# 12V_POWER_BULKHEAD.net
KiCad netlist of a schematic drawn in Altium Designer
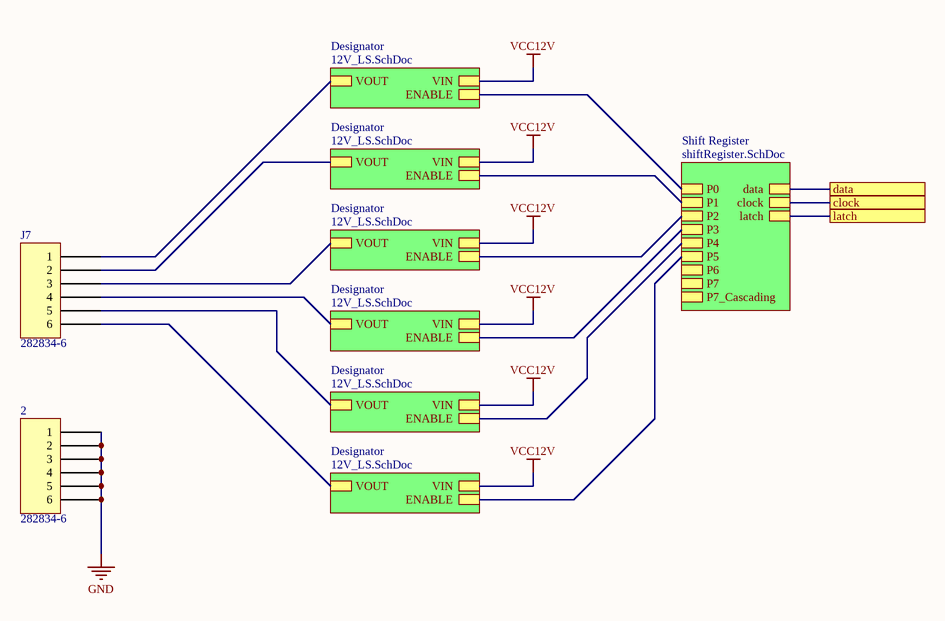
[diagram p0: 12V_POWER_BULKHEAD.SchDoc]

(export (version "E")
  (design (tool "Eeschema 10.0.6"))
  (components
    (comp (ref "2")
      (value "282834-6")
      (footprint "TE 282834-6")
      (description "TERM BLK 6P SIDE ENT 2.54MM PCB")
      (fields (field (name "MANUFACTURER") "TE Connectivity AMP Connectors") (field (name "VOLTAGE") "150V"))
      (libsource (lib "Celestial Altium Library - altium_library") (part "6 Pin"))
    )
    (comp (ref "J7")
      (value "282834-6")
      (footprint "TE 282834-6")
      (description "TERM BLK 6P SIDE ENT 2.54MM PCB")
      (fields (field (name "MANUFACTURER") "TE Connectivity AMP Connectors") (field (name "VOLTAGE") "150V"))
      (libsource (lib "Celestial Altium Library - altium_library") (part "6 Pin"))
    )
  )
  (nets
    (net (code "10") (name "/VOUT") (class "Default")
      (node (ref "J7") (pin "1") (pinfunction "1_1") (pintype "passive"))
    )
    (net (code "11") (name "/VOUT_1") (class "Default")
      (node (ref "J7") (pin "2") (pinfunction "2_2") (pintype "passive"))
    )
    (net (code "12") (name "/VOUT_2") (class "Default")
      (node (ref "J7") (pin "3") (pinfunction "3_3") (pintype "passive"))
    )
    (net (code "13") (name "/VOUT_3") (class "Default")
      (node (ref "J7") (pin "4") (pinfunction "4_4") (pintype "passive"))
    )
    (net (code "14") (name "/VOUT_4") (class "Default")
      (node (ref "J7") (pin "5") (pinfunction "5_5") (pintype "passive"))
    )
    (net (code "15") (name "/VOUT_5") (class "Default")
      (node (ref "J7") (pin "6") (pinfunction "6_6") (pintype "passive"))
    )
    (net (code "19") (name "GND") (class "Default")
      (node (ref "2") (pin "1") (pinfunction "1_1") (pintype "passive"))
      (node (ref "2") (pin "2") (pinfunction "2_2") (pintype "passive"))
      (node (ref "2") (pin "3") (pinfunction "3_3") (pintype "passive"))
      (node (ref "2") (pin "4") (pinfunction "4_4") (pintype "passive"))
      (node (ref "2") (pin "5") (pinfunction "5_5") (pintype "passive"))
      (node (ref "2") (pin "6") (pinfunction "6_6") (pintype "passive"))
    )
  )
)
